# CHANNEL.net
KiCad netlist of a schematic drawn in Altium Designer
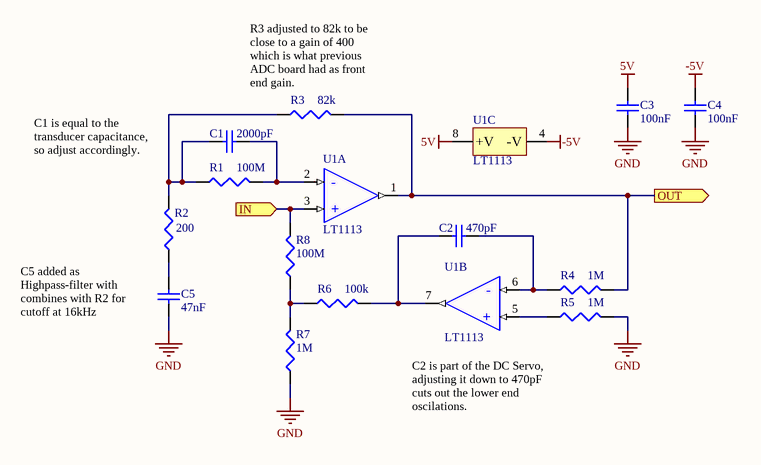
[diagram p0: CHANNEL.SchDoc]

(export (version "E")
  (design (tool "Eeschema 10.0.6"))
  (components
    (comp (ref "C1")
      (value "2000pF")
      (footprint "1608[0603]")
      (description "Capacitor (Semiconductor SIM Model)")
      (fields (field (name "Comment") "Cap Semi") (field (name "PUBLISHER") "Altium Limited"))
      (libsource (lib "Miscellaneous Devices") (part "Cap Semi"))
    )
    (comp (ref "C2")
      (value "470pF")
      (footprint "1608[0603]")
      (description "Capacitor (Semiconductor SIM Model)")
      (fields (field (name "Comment") "Cap Semi") (field (name "PUBLISHER") "Altium Limited"))
      (libsource (lib "Miscellaneous Devices") (part "Cap Semi"))
    )
    (comp (ref "C3")
      (value "100nF")
      (footprint "1608[0603]")
      (description "Capacitor (Semiconductor SIM Model)")
      (fields (field (name "Comment") "Cap Semi") (field (name "PUBLISHER") "Altium Limited"))
      (libsource (lib "Miscellaneous Devices") (part "Cap Semi"))
    )
    (comp (ref "C4")
      (value "100nF")
      (footprint "1608[0603]")
      (description "Capacitor (Semiconductor SIM Model)")
      (fields (field (name "Comment") "Cap Semi") (field (name "PUBLISHER") "Altium Limited"))
      (libsource (lib "Miscellaneous Devices") (part "Cap Semi"))
    )
    (comp (ref "C5")
      (value "47nF")
      (footprint "1608[0603]")
      (description "Capacitor (Semiconductor SIM Model)")
      (fields (field (name "Comment") "Cap Semi") (field (name "PUBLISHER") "Altium Limited"))
      (libsource (lib "Miscellaneous Devices") (part "Cap Semi"))
    )
    (comp (ref "R1")
      (value "100M")
      (footprint "J1-0603")
      (description "Resistor")
      (fields (field (name "Comment") "Res3") (field (name "PUBLISHER") "Altium Limited"))
      (libsource (lib "Miscellaneous Devices") (part "Res3"))
    )
    (comp (ref "R2")
      (value "200")
      (footprint "J1-0603")
      (description "Resistor")
      (fields (field (name "Comment") "Res3") (field (name "PUBLISHER") "Altium Limited"))
      (libsource (lib "Miscellaneous Devices") (part "Res3"))
    )
    (comp (ref "R3")
      (value "82k")
      (footprint "J1-0603")
      (description "Resistor")
      (fields (field (name "Comment") "Res3") (field (name "PUBLISHER") "Altium Limited"))
      (libsource (lib "Miscellaneous Devices") (part "Res3"))
    )
    (comp (ref "R4")
      (value "1M")
      (footprint "J1-0603")
      (description "Resistor")
      (fields (field (name "Comment") "Res3") (field (name "PUBLISHER") "Altium Limited"))
      (libsource (lib "Miscellaneous Devices") (part "Res3"))
    )
    (comp (ref "R5")
      (value "1M")
      (footprint "J1-0603")
      (description "Resistor")
      (fields (field (name "Comment") "Res3") (field (name "PUBLISHER") "Altium Limited"))
      (libsource (lib "Miscellaneous Devices") (part "Res3"))
    )
    (comp (ref "R6")
      (value "100k")
      (footprint "J1-0603")
      (description "Resistor")
      (fields (field (name "Comment") "Res3") (field (name "PUBLISHER") "Altium Limited"))
      (libsource (lib "Miscellaneous Devices") (part "Res3"))
    )
    (comp (ref "R7")
      (value "1M")
      (footprint "J1-0603")
      (description "Resistor")
      (fields (field (name "Comment") "Res3") (field (name "PUBLISHER") "Altium Limited"))
      (libsource (lib "Miscellaneous Devices") (part "Res3"))
    )
    (comp (ref "R8")
      (value "100M")
      (footprint "J1-0603")
      (description "Resistor")
      (fields (field (name "Comment") "Res3") (field (name "PUBLISHER") "Altium Limited"))
      (libsource (lib "Miscellaneous Devices") (part "Res3"))
    )
    (comp (ref "U1")
      (value "LT1113")
      (footprint "SO8_L")
      (description "LT1113 Opamp")
      (libsource (lib "") (part "LT1113_1"))
    )
  )
  (nets
    (net (code "1") (name "-5V") (class "Default")
      (node (ref "C4") (pin "2") (pinfunction "2_2") (pintype "passive"))
      (node (ref "U1") (pin "4") (pinfunction "-V_4") (pintype "power_in"))
    )
    (net (code "2") (name "/IN") (class "Default")
      (node (ref "R8") (pin "2") (pinfunction "2_2") (pintype "passive"))
      (node (ref "U1") (pin "3") (pinfunction "+_3") (pintype "input"))
    )
    (net (code "3") (name "/OUT") (class "Default")
      (node (ref "R3") (pin "2") (pinfunction "2_2") (pintype "passive"))
      (node (ref "R4") (pin "2") (pinfunction "2_2") (pintype "passive"))
      (node (ref "U1") (pin "1") (pinfunction "OUTA_1") (pintype "output"))
    )
    (net (code "4") (name "5V") (class "Default")
      (node (ref "C3") (pin "2") (pinfunction "2_2") (pintype "passive"))
      (node (ref "U1") (pin "8") (pinfunction "+V_8") (pintype "power_in"))
    )
    (net (code "5") (name "GND") (class "Default")
      (node (ref "C3") (pin "1") (pinfunction "1_1") (pintype "passive"))
      (node (ref "C4") (pin "1") (pinfunction "1_1") (pintype "passive"))
      (node (ref "C5") (pin "1") (pinfunction "1_1") (pintype "passive"))
      (node (ref "R5") (pin "2") (pinfunction "2_2") (pintype "passive"))
      (node (ref "R7") (pin "1") (pinfunction "1_1") (pintype "passive"))
    )
    (net (code "6") (name "Net-(C1-Pad1)") (class "Default")
      (node (ref "C1") (pin "1") (pinfunction "1_1") (pintype "passive"))
      (node (ref "R1") (pin "1") (pinfunction "1_1") (pintype "passive"))
      (node (ref "R2") (pin "2") (pinfunction "2_2") (pintype "passive"))
      (node (ref "R3") (pin "1") (pinfunction "1_1") (pintype "passive"))
    )
    (net (code "7") (name "Net-(C5-Pad2)") (class "Default")
      (node (ref "C5") (pin "2") (pinfunction "2_2") (pintype "passive"))
      (node (ref "R2") (pin "1") (pinfunction "1_1") (pintype "passive"))
    )
    (net (code "8") (name "Net-(R6-Pad1)") (class "Default")
      (node (ref "R6") (pin "1") (pinfunction "1_1") (pintype "passive"))
      (node (ref "R7") (pin "2") (pinfunction "2_2") (pintype "passive"))
      (node (ref "R8") (pin "1") (pinfunction "1_1") (pintype "passive"))
    )
    (net (code "9") (name "Net-(U1A--)") (class "Default")
      (node (ref "C1") (pin "2") (pinfunction "2_2") (pintype "passive"))
      (node (ref "R1") (pin "2") (pinfunction "2_2") (pintype "passive"))
      (node (ref "U1") (pin "2") (pinfunction "-_2") (pintype "input"))
    )
    (net (code "10") (name "Net-(U1B-+)") (class "Default")
      (node (ref "R5") (pin "1") (pinfunction "1_1") (pintype "passive"))
      (node (ref "U1") (pin "5") (pinfunction "+_5") (pintype "input"))
    )
    (net (code "11") (name "Net-(U1B--)") (class "Default")
      (node (ref "C2") (pin "2") (pinfunction "2_2") (pintype "passive"))
      (node (ref "R4") (pin "1") (pinfunction "1_1") (pintype "passive"))
      (node (ref "U1") (pin "6") (pinfunction "-_6") (pintype "input"))
    )
    (net (code "12") (name "Net-(U1B-OUTA)") (class "Default")
      (node (ref "C2") (pin "1") (pinfunction "1_1") (pintype "passive"))
      (node (ref "R6") (pin "2") (pinfunction "2_2") (pintype "passive"))
      (node (ref "U1") (pin "7") (pinfunction "OUTA_7") (pintype "output"))
    )
  )
)
